# Channel_Fix_OPEN_COLLECTOR.net
KiCad netlist of a schematic drawn in Altium Designer
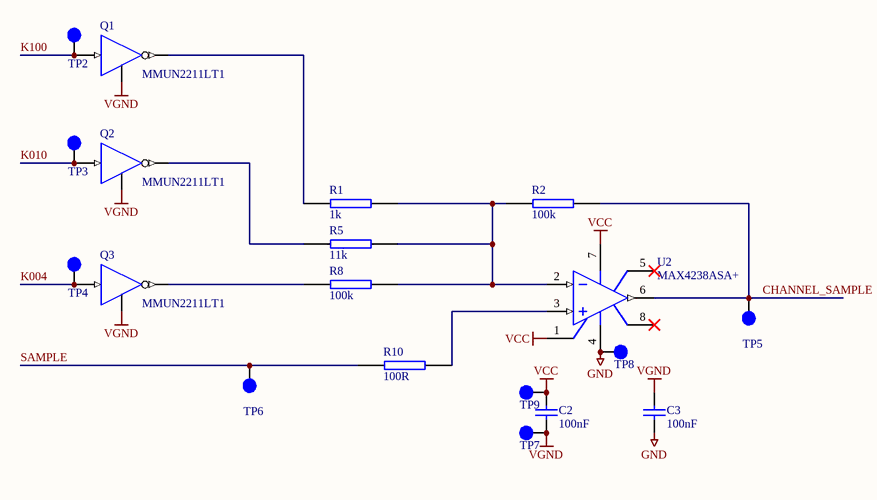
[diagram p0: Channel Fix (OPEN COLLECTOR).SchDoc]

(export (version "E")
  (design (tool "Eeschema 10.0.6"))
  (components
    (comp (ref "C2")
      (value "100nF")
      (footprint "CAP (3D) - 0805")
      (description "Capacitor")
      (libsource (lib "Miscellaneous Devices") (part "Cap"))
    )
    (comp (ref "C3")
      (value "100nF")
      (footprint "CAP (3D) - 0805")
      (description "Capacitor")
      (libsource (lib "Miscellaneous Devices") (part "Cap"))
    )
    (comp (ref "Q1")
      (value "MMUN2211LT1")
      (footprint "SOT23-3L")
      (fields
        (field (name "MOUSER PART NO.") "863-MMUN2211LT1G")
        (field (name "FARNELL PART NO.") "9556648RL")
        (field (name "MANUFACTURER") "ON Semiconductor")
      )
      (libsource (lib "NASCO") (part "MMUN221LT1 NPN DIGITAL TRANSISTOR"))
    )
    (comp (ref "Q2")
      (value "MMUN2211LT1")
      (footprint "SOT23-3L")
      (fields
        (field (name "MOUSER PART NO.") "863-MMUN2211LT1G")
        (field (name "FARNELL PART NO.") "9556648RL")
        (field (name "MANUFACTURER") "ON Semiconductor")
      )
      (libsource (lib "NASCO") (part "MMUN221LT1 NPN DIGITAL TRANSISTOR"))
    )
    (comp (ref "Q3")
      (value "MMUN2211LT1")
      (footprint "SOT23-3L")
      (fields
        (field (name "MOUSER PART NO.") "863-MMUN2211LT1G")
        (field (name "FARNELL PART NO.") "9556648RL")
        (field (name "MANUFACTURER") "ON Semiconductor")
      )
      (libsource (lib "NASCO") (part "MMUN221LT1 NPN DIGITAL TRANSISTOR"))
    )
    (comp (ref "R1")
      (value "1k")
      (footprint "RES (3D) - 0805")
      (description "RESISTOR SMD 0603")
      (libsource (lib "NASCO") (part "RES SMD 0603"))
    )
    (comp (ref "R2")
      (value "100k")
      (footprint "RES (3D) - 0805")
      (description "RESISTOR SMD 0603")
      (libsource (lib "NASCO") (part "RES SMD 0603"))
    )
    (comp (ref "R5")
      (value "11k")
      (footprint "RES (3D) - 0805")
      (description "RESISTOR SMD 0603")
      (libsource (lib "NASCO") (part "RES SMD 0603"))
    )
    (comp (ref "R8")
      (value "100k")
      (footprint "RES (3D) - 0805")
      (description "RESISTOR SMD 0603")
      (libsource (lib "NASCO") (part "RES SMD 0603"))
    )
    (comp (ref "R10")
      (value "100R")
      (footprint "RES (3D) - 0805")
      (description "RESISTOR SMD 0603")
      (libsource (lib "NASCO") (part "RES SMD 0603"))
    )
    (comp (ref "TP2") (value "TestPoint") (footprint "TP") (libsource (lib "NASCO") (part "TestPoint")))
    (comp (ref "TP3") (value "TestPoint") (footprint "TP") (libsource (lib "NASCO") (part "TestPoint")))
    (comp (ref "TP4") (value "TestPoint") (footprint "TP") (libsource (lib "NASCO") (part "TestPoint")))
    (comp (ref "TP5") (value "TestPoint") (footprint "TP") (libsource (lib "NASCO") (part "TestPoint")))
    (comp (ref "TP6") (value "TestPoint") (footprint "TP") (libsource (lib "NASCO") (part "TestPoint")))
    (comp (ref "TP7") (value "TestPoint") (footprint "TP") (libsource (lib "NASCO") (part "TestPoint")))
    (comp (ref "TP8") (value "TestPoint") (footprint "TP") (libsource (lib "NASCO") (part "TestPoint")))
    (comp (ref "TP9") (value "TestPoint") (footprint "TP") (libsource (lib "NASCO") (part "TestPoint")))
    (comp (ref "U2")
      (value "MAX4238ASA+")
      (footprint "SO-8")
      (description "Single Voltage-Feedback Operational Amplifier")
      (fields (field (name "PUBLISHER") "Altium Limited"))
      (libsource (lib "Maxim Operational Amplifier") (part "MAX495CSA"))
    )
  )
  (nets
    (net (code "1") (name "/CHANNEL_SAMPLE") (class "Default")
      (node (ref "R2") (pin "2") (pinfunction "2_2") (pintype "passive"))
      (node (ref "TP5") (pin "1") (pinfunction "1_1") (pintype "passive"))
      (node (ref "U2") (pin "6") (pinfunction "OUT_6") (pintype "output"))
    )
    (net (code "2") (name "/K004") (class "Default")
      (node (ref "Q3") (pin "1") (pinfunction "B_1") (pintype "input"))
      (node (ref "TP4") (pin "1") (pinfunction "1_1") (pintype "passive"))
    )
    (net (code "3") (name "/K010") (class "Default")
      (node (ref "Q2") (pin "1") (pinfunction "B_1") (pintype "input"))
      (node (ref "TP3") (pin "1") (pinfunction "1_1") (pintype "passive"))
    )
    (net (code "4") (name "/K100") (class "Default")
      (node (ref "Q1") (pin "1") (pinfunction "B_1") (pintype "input"))
      (node (ref "TP2") (pin "1") (pinfunction "1_1") (pintype "passive"))
    )
    (net (code "5") (name "/SAMPLE") (class "Default")
      (node (ref "R10") (pin "1") (pinfunction "1_1") (pintype "passive"))
      (node (ref "TP6") (pin "1") (pinfunction "1_1") (pintype "passive"))
    )
    (net (code "6") (name "GND") (class "Default")
      (node (ref "C3") (pin "1") (pinfunction "1_1") (pintype "passive"))
      (node (ref "TP8") (pin "1") (pinfunction "1_1") (pintype "passive"))
      (node (ref "U2") (pin "4") (pinfunction "VEE_4") (pintype "power_in"))
    )
    (net (code "7") (name "Net-(Q1-C)") (class "Default")
      (node (ref "Q1") (pin "3") (pinfunction "C_3") (pintype "output"))
      (node (ref "R1") (pin "1") (pinfunction "1_1") (pintype "passive"))
    )
    (net (code "8") (name "Net-(Q2-C)") (class "Default")
      (node (ref "Q2") (pin "3") (pinfunction "C_3") (pintype "output"))
      (node (ref "R5") (pin "1") (pinfunction "1_1") (pintype "passive"))
    )
    (net (code "9") (name "Net-(Q3-C)") (class "Default")
      (node (ref "Q3") (pin "3") (pinfunction "C_3") (pintype "output"))
      (node (ref "R8") (pin "1") (pinfunction "1_1") (pintype "passive"))
    )
    (net (code "10") (name "Net-(U2-IN+)") (class "Default")
      (node (ref "R10") (pin "2") (pinfunction "2_2") (pintype "passive"))
      (node (ref "U2") (pin "3") (pinfunction "IN+_3") (pintype "input"))
    )
    (net (code "11") (name "Net-(U2-IN-)") (class "Default")
      (node (ref "R1") (pin "2") (pinfunction "2_2") (pintype "passive"))
      (node (ref "R2") (pin "1") (pinfunction "1_1") (pintype "passive"))
      (node (ref "R5") (pin "2") (pinfunction "2_2") (pintype "passive"))
      (node (ref "R8") (pin "2") (pinfunction "2_2") (pintype "passive"))
      (node (ref "U2") (pin "2") (pinfunction "IN-_2") (pintype "input"))
    )
    (net (code "12") (name "VCC") (class "Default")
      (node (ref "C2") (pin "2") (pinfunction "2_2") (pintype "passive"))
      (node (ref "TP9") (pin "1") (pinfunction "1_1") (pintype "passive"))
      (node (ref "U2") (pin "1") (pinfunction "NULL_1") (pintype "passive"))
      (node (ref "U2") (pin "7") (pinfunction "VCC_7") (pintype "power_in"))
    )
    (net (code "13") (name "VGND") (class "Default")
      (node (ref "C2") (pin "1") (pinfunction "1_1") (pintype "passive"))
      (node (ref "C3") (pin "2") (pinfunction "2_2") (pintype "passive"))
      (node (ref "Q1") (pin "2") (pinfunction "E_2") (pintype "passive"))
      (node (ref "Q2") (pin "2") (pinfunction "E_2") (pintype "passive"))
      (node (ref "Q3") (pin "2") (pinfunction "E_2") (pintype "passive"))
      (node (ref "TP7") (pin "1") (pinfunction "1_1") (pintype "passive"))
    )
    (net (code "14") (name "unconnected-(U2-NC-Pad8)") (class "Default")
      (node (ref "U2") (pin "8") (pinfunction "NC_8") (pintype "passive+no_connect"))
    )
    (net (code "15") (name "unconnected-(U2-NULL-Pad5)") (class "Default")
      (node (ref "U2") (pin "5") (pinfunction "NULL_5") (pintype "passive+no_connect"))
    )
  )
)
